# cable_3.net
KiCad netlist of a schematic drawn in EAGLE
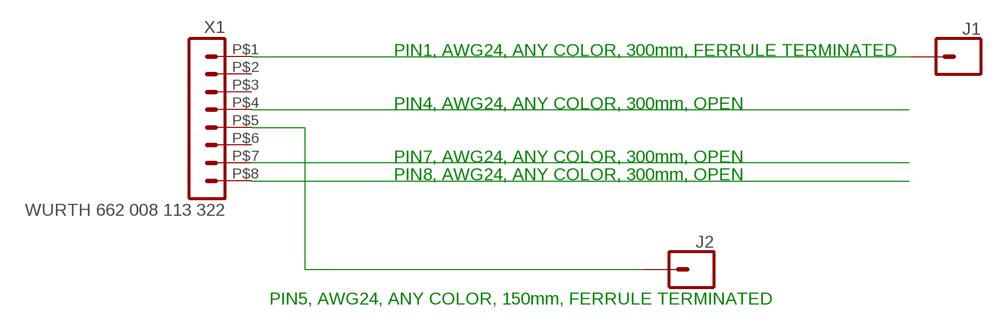
[diagram p0: schematic, sheet 1]

(export (version "E")
  (design (tool "Eeschema 10.0.6"))
  (components
    (comp (ref "J1")
      (value "CONN_01")
      (footprint "eagle-import:1X01")
      (libsource (lib "eagle-import") (part "CONN_01"))
    )
    (comp (ref "J2")
      (value "CONN_01")
      (footprint "eagle-import:1X01")
      (libsource (lib "eagle-import") (part "CONN_01"))
    )
    (comp (ref "X1")
      (value "WURTH 662 008 113 322")
      (footprint "eagle-import:43045-0800")
      (libsource (lib "eagle-import") (part "HEADER_POS8_?43045-0800"))
    )
  )
  (nets
    (net (code "1") (name "Net-(X1-1)") (class "Default")
      (node (ref "J1") (pin "1") (pinfunction "1_1") (pintype "passive"))
      (node (ref "X1") (pin "P$1") (pinfunction "1_P$1") (pintype "passive"))
    )
    (net (code "2") (name "Net-(X1-5)") (class "Default")
      (node (ref "J2") (pin "1") (pinfunction "1_1") (pintype "passive"))
      (node (ref "X1") (pin "P$5") (pinfunction "5_P$5") (pintype "passive"))
    )
    (net (code "3") (name "unconnected-(X1-2-PadP$2)") (class "Default")
      (node (ref "X1") (pin "P$2") (pinfunction "2_P$2") (pintype "passive"))
    )
    (net (code "4") (name "unconnected-(X1-3-PadP$3)") (class "Default")
      (node (ref "X1") (pin "P$3") (pinfunction "3_P$3") (pintype "passive"))
    )
    (net (code "5") (name "unconnected-(X1-4-PadP$4)") (class "Default")
      (node (ref "X1") (pin "P$4") (pinfunction "4_P$4") (pintype "passive"))
    )
    (net (code "6") (name "unconnected-(X1-6-PadP$6)") (class "Default")
      (node (ref "X1") (pin "P$6") (pinfunction "6_P$6") (pintype "passive"))
    )
    (net (code "7") (name "unconnected-(X1-7-PadP$7)") (class "Default")
      (node (ref "X1") (pin "P$7") (pinfunction "7_P$7") (pintype "passive"))
    )
    (net (code "8") (name "unconnected-(X1-8-PadP$8)") (class "Default")
      (node (ref "X1") (pin "P$8") (pinfunction "8_P$8") (pintype "passive"))
    )
  )
)
